# reflow.net
KiCad netlist of a schematic drawn in EAGLE
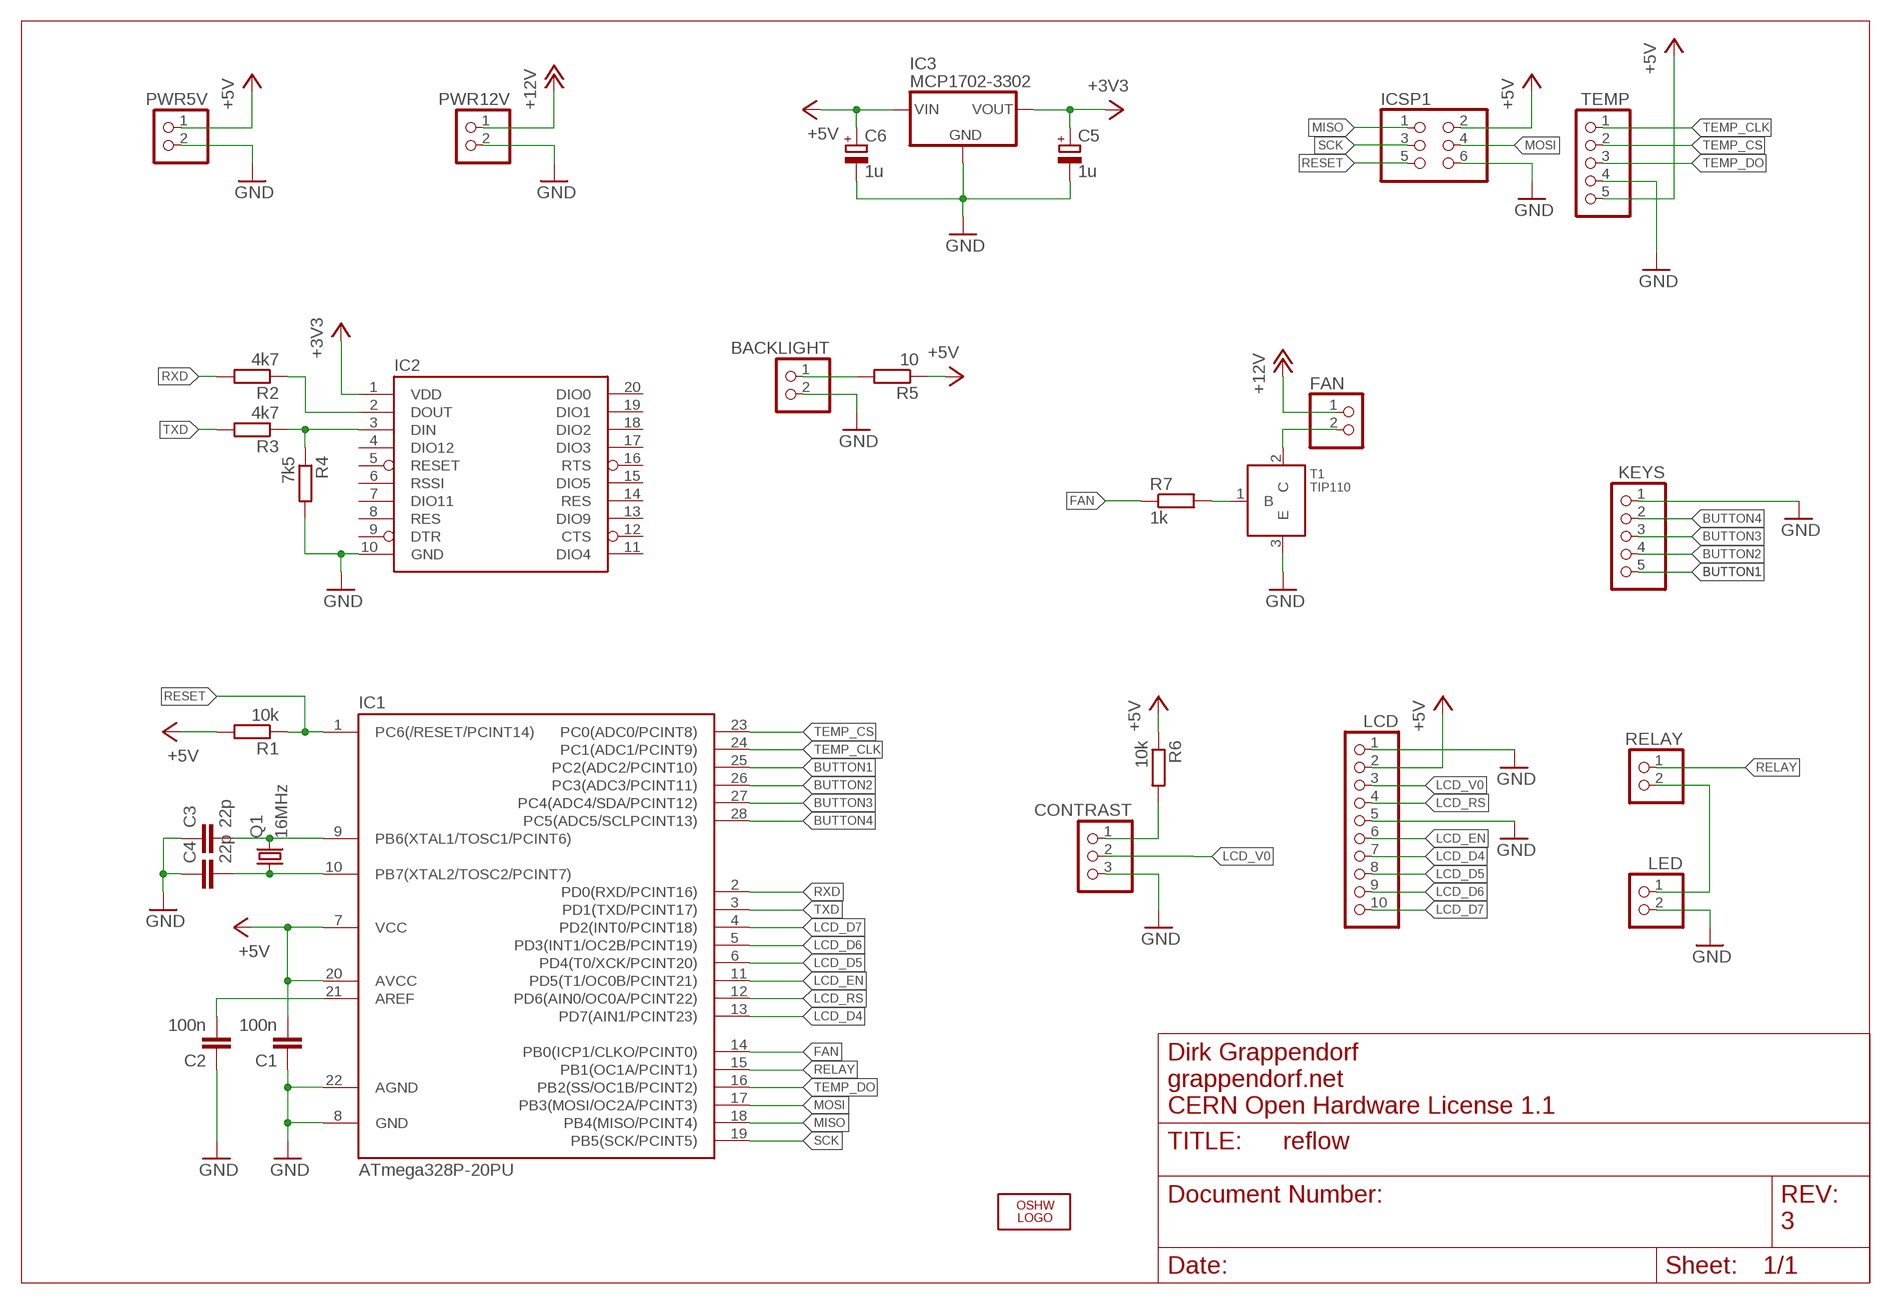
[diagram p0: schematic, sheet 1]

(export (version "E")
  (design (tool "Eeschema 10.0.6"))
  (components
    (comp (ref "BACKLIGHT")
      (value "PINHD-1X2")
      (footprint "eagle-import:1X02")
      (libsource (lib "eagle-import") (part "PINHD-1X2"))
    )
    (comp (ref "C1")
      (value "100n")
      (footprint "eagle-import:C025-024X044")
      (libsource (lib "eagle-import") (part "C-EU025-024X044"))
    )
    (comp (ref "C2")
      (value "100n")
      (footprint "eagle-import:C025-024X044")
      (libsource (lib "eagle-import") (part "C-EU025-024X044"))
    )
    (comp (ref "C3")
      (value "22p")
      (footprint "eagle-import:C025-025X050")
      (libsource (lib "eagle-import") (part "C-EU025-025X050"))
    )
    (comp (ref "C4")
      (value "22p")
      (footprint "eagle-import:C025-025X050")
      (libsource (lib "eagle-import") (part "C-EU025-025X050"))
    )
    (comp (ref "C5")
      (value "1u")
      (footprint "eagle-import:E2,5-5")
      (libsource (lib "eagle-import") (part "CPOL-EUE2.5-5"))
    )
    (comp (ref "C6")
      (value "1u")
      (footprint "eagle-import:E2,5-5")
      (libsource (lib "eagle-import") (part "CPOL-EUE2.5-5"))
    )
    (comp (ref "CONTRAST")
      (value "PINHD-1X3")
      (footprint "eagle-import:1X03")
      (libsource (lib "eagle-import") (part "PINHD-1X3"))
    )
    (comp (ref "FAN")
      (value "PINHD-1X2")
      (footprint "eagle-import:1X02")
      (libsource (lib "eagle-import") (part "PINHD-1X2"))
    )
    (comp (ref "IC1")
      (value "ATmega328P-20PU")
      (footprint "eagle-import:DIL28-3")
      (libsource (lib "eagle-import") (part "ATMEGA48/88/168-PU"))
    )
    (comp (ref "IC2")
      (value "XBEE-1B1")
      (footprint "eagle-import:XBEE-1")
      (libsource (lib "eagle-import") (part "XBEE-1B1"))
    )
    (comp (ref "IC3")
      (value "MCP1702-3302")
      (footprint "eagle-import:MCP1702")
      (libsource (lib "eagle-import") (part "MCP1702"))
    )
    (comp (ref "ICSP1")
      (value "PINHD-2X03_2.54")
      (footprint "eagle-import:2X03")
      (libsource (lib "eagle-import") (part "PINHD-2X03_2.54"))
    )
    (comp (ref "KEYS")
      (value "PINHD-1X5")
      (footprint "eagle-import:1X05")
      (libsource (lib "eagle-import") (part "PINHD-1X5"))
    )
    (comp (ref "LCD")
      (value "PINHD-1X10")
      (footprint "eagle-import:1X10")
      (libsource (lib "eagle-import") (part "PINHD-1X10"))
    )
    (comp (ref "LED")
      (value "PINHD-1X2")
      (footprint "eagle-import:1X02")
      (libsource (lib "eagle-import") (part "PINHD-1X2"))
    )
    (comp (ref "LOGO1")
      (value "OSHW_LOGO_10MILX0350-NT-BOTTOM")
      (footprint "eagle-import:OSHW_10X350_NOTEXT_BOTTOM")
      (libsource (lib "eagle-import") (part "OSHW_LOGO_10MILX0350-NT-BOTTOM"))
    )
    (comp (ref "PWR5V")
      (value "PINHD-1X2")
      (footprint "eagle-import:1X02")
      (libsource (lib "eagle-import") (part "PINHD-1X2"))
    )
    (comp (ref "PWR12V")
      (value "PINHD-1X2")
      (footprint "eagle-import:1X02")
      (libsource (lib "eagle-import") (part "PINHD-1X2"))
    )
    (comp (ref "Q1")
      (value "16MHz")
      (footprint "eagle-import:HC49U-V")
      (libsource (lib "eagle-import") (part "CRYSTALHC49U-V"))
    )
    (comp (ref "R1")
      (value "10k")
      (footprint "eagle-import:0204_7")
      (libsource (lib "eagle-import") (part "R-EU_0204/7"))
    )
    (comp (ref "R2")
      (value "4k7")
      (footprint "eagle-import:0204_7")
      (libsource (lib "eagle-import") (part "R-EU_0204/7"))
    )
    (comp (ref "R3")
      (value "4k7")
      (footprint "eagle-import:0204_7")
      (libsource (lib "eagle-import") (part "R-EU_0204/7"))
    )
    (comp (ref "R4")
      (value "7k5")
      (footprint "eagle-import:0204_7")
      (libsource (lib "eagle-import") (part "R-EU_0204/7"))
    )
    (comp (ref "R5")
      (value "10")
      (footprint "eagle-import:0204_7")
      (libsource (lib "eagle-import") (part "R-EU_0204/7"))
    )
    (comp (ref "R6")
      (value "10k")
      (footprint "eagle-import:0204_7")
      (libsource (lib "eagle-import") (part "R-EU_0204/7"))
    )
    (comp (ref "R7")
      (value "1k")
      (footprint "eagle-import:0204_7")
      (libsource (lib "eagle-import") (part "R-EU_0204/7"))
    )
    (comp (ref "RELAY")
      (value "PINHD-1X2")
      (footprint "eagle-import:1X02")
      (libsource (lib "eagle-import") (part "PINHD-1X2"))
    )
    (comp (ref "T1")
      (value "TIP110")
      (footprint "eagle-import:T0220")
      (libsource (lib "eagle-import") (part "TIP112"))
    )
    (comp (ref "TEMP")
      (value "PINHD-1X5")
      (footprint "eagle-import:1X05")
      (libsource (lib "eagle-import") (part "PINHD-1X5"))
    )
  )
  (nets
    (net (code "1") (name "+3V3") (class "Default")
      (node (ref "C5") (pin "+") (pinfunction "+_+") (pintype "passive"))
      (node (ref "IC2") (pin "1") (pinfunction "VDD_1") (pintype "power_in"))
      (node (ref "IC3") (pin "VOUT") (pinfunction "OUT_VOUT") (pintype "passive"))
    )
    (net (code "2") (name "+5V") (class "Default")
      (node (ref "C1") (pin "2") (pinfunction "2_2") (pintype "passive"))
      (node (ref "C6") (pin "+") (pinfunction "+_+") (pintype "passive"))
      (node (ref "IC1") (pin "20") (pinfunction "AVCC_20") (pintype "passive"))
      (node (ref "IC1") (pin "7") (pinfunction "VCC_7") (pintype "power_in"))
      (node (ref "IC3") (pin "VIN") (pinfunction "IN_VIN") (pintype "input"))
      (node (ref "ICSP1") (pin "2") (pinfunction "2_2") (pintype "passive"))
      (node (ref "LCD") (pin "2") (pinfunction "2_2") (pintype "passive"))
      (node (ref "PWR5V") (pin "1") (pinfunction "1_1") (pintype "passive"))
      (node (ref "R1") (pin "2") (pinfunction "2_2") (pintype "passive"))
      (node (ref "R5") (pin "1") (pinfunction "1_1") (pintype "passive"))
      (node (ref "R6") (pin "1") (pinfunction "1_1") (pintype "passive"))
      (node (ref "TEMP") (pin "5") (pinfunction "5_5") (pintype "passive"))
    )
    (net (code "3") (name "+12V") (class "Default")
      (node (ref "FAN") (pin "1") (pinfunction "1_1") (pintype "passive"))
      (node (ref "PWR12V") (pin "1") (pinfunction "1_1") (pintype "passive"))
    )
    (net (code "4") (name "BUTTON1") (class "Default")
      (node (ref "IC1") (pin "25") (pinfunction "PC2(ADC2/PCINT10)_25") (pintype "bidirectional"))
      (node (ref "KEYS") (pin "5") (pinfunction "5_5") (pintype "passive"))
    )
    (net (code "5") (name "BUTTON2") (class "Default")
      (node (ref "IC1") (pin "26") (pinfunction "PC3(ADC3/PCINT11)_26") (pintype "bidirectional"))
      (node (ref "KEYS") (pin "4") (pinfunction "4_4") (pintype "passive"))
    )
    (net (code "6") (name "BUTTON3") (class "Default")
      (node (ref "IC1") (pin "27") (pinfunction "PC4(ADC4/SDA/PCINT12)_27") (pintype "bidirectional"))
      (node (ref "KEYS") (pin "3") (pinfunction "3_3") (pintype "passive"))
    )
    (net (code "7") (name "BUTTON4") (class "Default")
      (node (ref "IC1") (pin "28") (pinfunction "PC5(ADC5/SCLPCINT13)_28") (pintype "bidirectional"))
      (node (ref "KEYS") (pin "2") (pinfunction "2_2") (pintype "passive"))
    )
    (net (code "8") (name "FAN") (class "Default")
      (node (ref "IC1") (pin "14") (pinfunction "PB0(ICP1/CLKO/PCINT0)_14") (pintype "bidirectional"))
      (node (ref "R7") (pin "1") (pinfunction "1_1") (pintype "passive"))
    )
    (net (code "9") (name "GND") (class "Default")
      (node (ref "BACKLIGHT") (pin "2") (pinfunction "2_2") (pintype "passive"))
      (node (ref "C1") (pin "1") (pinfunction "1_1") (pintype "passive"))
      (node (ref "C2") (pin "1") (pinfunction "1_1") (pintype "passive"))
      (node (ref "C3") (pin "1") (pinfunction "1_1") (pintype "passive"))
      (node (ref "C4") (pin "1") (pinfunction "1_1") (pintype "passive"))
      (node (ref "C5") (pin "-") (pinfunction "-_-") (pintype "passive"))
      (node (ref "C6") (pin "-") (pinfunction "-_-") (pintype "passive"))
      (node (ref "CONTRAST") (pin "3") (pinfunction "3_3") (pintype "passive"))
      (node (ref "IC1") (pin "22") (pinfunction "AGND_22") (pintype "power_in"))
      (node (ref "IC1") (pin "8") (pinfunction "GND_8") (pintype "power_in"))
      (node (ref "IC2") (pin "10") (pinfunction "GND_10") (pintype "power_in"))
      (node (ref "IC3") (pin "GND") (pinfunction "GND_GND") (pintype "input"))
      (node (ref "ICSP1") (pin "6") (pinfunction "6_6") (pintype "passive"))
      (node (ref "KEYS") (pin "1") (pinfunction "1_1") (pintype "passive"))
      (node (ref "LCD") (pin "1") (pinfunction "1_1") (pintype "passive"))
      (node (ref "LCD") (pin "5") (pinfunction "5_5") (pintype "passive"))
      (node (ref "LED") (pin "2") (pinfunction "2_2") (pintype "passive"))
      (node (ref "PWR12V") (pin "2") (pinfunction "2_2") (pintype "passive"))
      (node (ref "PWR5V") (pin "2") (pinfunction "2_2") (pintype "passive"))
      (node (ref "R4") (pin "2") (pinfunction "2_2") (pintype "passive"))
      (node (ref "T1") (pin "3") (pinfunction "E_3") (pintype "bidirectional"))
      (node (ref "TEMP") (pin "4") (pinfunction "4_4") (pintype "passive"))
    )
    (net (code "10") (name "LCD_D4") (class "Default")
      (node (ref "IC1") (pin "13") (pinfunction "PD7(AIN1/PCINT23)_13") (pintype "bidirectional"))
      (node (ref "LCD") (pin "7") (pinfunction "7_7") (pintype "passive"))
    )
    (net (code "11") (name "LCD_D5") (class "Default")
      (node (ref "IC1") (pin "6") (pinfunction "PD4(T0/XCK/PCINT20)_6") (pintype "bidirectional"))
      (node (ref "LCD") (pin "8") (pinfunction "8_8") (pintype "passive"))
    )
    (net (code "12") (name "LCD_D6") (class "Default")
      (node (ref "IC1") (pin "5") (pinfunction "PD3(INT1/OC2B/PCINT19)_5") (pintype "bidirectional"))
      (node (ref "LCD") (pin "9") (pinfunction "9_9") (pintype "passive"))
    )
    (net (code "13") (name "LCD_D7") (class "Default")
      (node (ref "IC1") (pin "4") (pinfunction "PD2(INT0/PCINT18)_4") (pintype "bidirectional"))
      (node (ref "LCD") (pin "10") (pinfunction "10_10") (pintype "passive"))
    )
    (net (code "14") (name "LCD_EN") (class "Default")
      (node (ref "IC1") (pin "11") (pinfunction "PD5(T1/OC0B/PCINT21)_11") (pintype "bidirectional"))
      (node (ref "LCD") (pin "6") (pinfunction "6_6") (pintype "passive"))
    )
    (net (code "15") (name "LCD_RS") (class "Default")
      (node (ref "IC1") (pin "12") (pinfunction "PD6(AIN0/OC0A/PCINT22)_12") (pintype "bidirectional"))
      (node (ref "LCD") (pin "4") (pinfunction "4_4") (pintype "passive"))
    )
    (net (code "16") (name "LCD_V0") (class "Default")
      (node (ref "CONTRAST") (pin "2") (pinfunction "2_2") (pintype "passive"))
      (node (ref "LCD") (pin "3") (pinfunction "3_3") (pintype "passive"))
    )
    (net (code "17") (name "MISO") (class "Default")
      (node (ref "IC1") (pin "18") (pinfunction "PB4(MISO/PCINT4)_18") (pintype "bidirectional"))
      (node (ref "ICSP1") (pin "1") (pinfunction "1_1") (pintype "passive"))
    )
    (net (code "18") (name "MOSI") (class "Default")
      (node (ref "IC1") (pin "17") (pinfunction "PB3(MOSI/OC2A/PCINT3)_17") (pintype "bidirectional"))
      (node (ref "ICSP1") (pin "4") (pinfunction "4_4") (pintype "passive"))
    )
    (net (code "19") (name "Net-(BACKLIGHT-Pad1)") (class "Default")
      (node (ref "BACKLIGHT") (pin "1") (pinfunction "1_1") (pintype "passive"))
      (node (ref "R5") (pin "2") (pinfunction "2_2") (pintype "passive"))
    )
    (net (code "20") (name "Net-(CONTRAST-Pad1)") (class "Default")
      (node (ref "CONTRAST") (pin "1") (pinfunction "1_1") (pintype "passive"))
      (node (ref "R6") (pin "2") (pinfunction "2_2") (pintype "passive"))
    )
    (net (code "21") (name "Net-(IC1-AREF)") (class "Default")
      (node (ref "C2") (pin "2") (pinfunction "2_2") (pintype "passive"))
      (node (ref "IC1") (pin "21") (pinfunction "AREF_21") (pintype "passive"))
    )
    (net (code "22") (name "Net-(IC1-PB6(XTAL1{slash}TOSC1{slash}PCINT6))") (class "Default")
      (node (ref "C3") (pin "2") (pinfunction "2_2") (pintype "passive"))
      (node (ref "IC1") (pin "9") (pinfunction "PB6(XTAL1/TOSC1/PCINT6)_9") (pintype "bidirectional"))
      (node (ref "Q1") (pin "2") (pinfunction "2_2") (pintype "passive"))
    )
    (net (code "23") (name "Net-(IC1-PB7(XTAL2{slash}TOSC2{slash}PCINT7))") (class "Default")
      (node (ref "C4") (pin "2") (pinfunction "2_2") (pintype "passive"))
      (node (ref "IC1") (pin "10") (pinfunction "PB7(XTAL2/TOSC2/PCINT7)_10") (pintype "bidirectional"))
      (node (ref "Q1") (pin "1") (pinfunction "1_1") (pintype "passive"))
    )
    (net (code "24") (name "Net-(IC2-DIN)") (class "Default")
      (node (ref "IC2") (pin "3") (pinfunction "DIN_3") (pintype "input"))
      (node (ref "R3") (pin "1") (pinfunction "1_1") (pintype "passive"))
      (node (ref "R4") (pin "1") (pinfunction "1_1") (pintype "passive"))
    )
    (net (code "25") (name "Net-(IC2-DOUT)") (class "Default")
      (node (ref "IC2") (pin "2") (pinfunction "DOUT_2") (pintype "output"))
      (node (ref "R2") (pin "1") (pinfunction "1_1") (pintype "passive"))
    )
    (net (code "26") (name "Net-(LED-Pad1)") (class "Default")
      (node (ref "LED") (pin "1") (pinfunction "1_1") (pintype "passive"))
      (node (ref "RELAY") (pin "2") (pinfunction "2_2") (pintype "passive"))
    )
    (net (code "27") (name "Net-(T1-B)") (class "Default")
      (node (ref "R7") (pin "2") (pinfunction "2_2") (pintype "passive"))
      (node (ref "T1") (pin "1") (pinfunction "B_1") (pintype "bidirectional"))
    )
    (net (code "28") (name "Net-(T1-C)") (class "Default")
      (node (ref "FAN") (pin "2") (pinfunction "2_2") (pintype "passive"))
      (node (ref "T1") (pin "2") (pinfunction "C_2") (pintype "bidirectional"))
    )
    (net (code "29") (name "RELAY") (class "Default")
      (node (ref "IC1") (pin "15") (pinfunction "PB1(OC1A/PCINT1)_15") (pintype "bidirectional"))
      (node (ref "RELAY") (pin "1") (pinfunction "1_1") (pintype "passive"))
    )
    (net (code "30") (name "RESET") (class "Default")
      (node (ref "IC1") (pin "1") (pinfunction "PC6(/RESET/PCINT14)_1") (pintype "bidirectional"))
      (node (ref "ICSP1") (pin "5") (pinfunction "5_5") (pintype "passive"))
      (node (ref "R1") (pin "1") (pinfunction "1_1") (pintype "passive"))
    )
    (net (code "31") (name "RXD") (class "Default")
      (node (ref "IC1") (pin "2") (pinfunction "PD0(RXD/PCINT16)_2") (pintype "bidirectional"))
      (node (ref "R2") (pin "2") (pinfunction "2_2") (pintype "passive"))
    )
    (net (code "32") (name "SCK") (class "Default")
      (node (ref "IC1") (pin "19") (pinfunction "PB5(SCK/PCINT5)_19") (pintype "bidirectional"))
      (node (ref "ICSP1") (pin "3") (pinfunction "3_3") (pintype "passive"))
    )
    (net (code "33") (name "TEMP_CLK") (class "Default")
      (node (ref "IC1") (pin "24") (pinfunction "PC1(ADC1/PCINT9)_24") (pintype "bidirectional"))
      (node (ref "TEMP") (pin "1") (pinfunction "1_1") (pintype "passive"))
    )
    (net (code "34") (name "TEMP_CS") (class "Default")
      (node (ref "IC1") (pin "23") (pinfunction "PC0(ADC0/PCINT8)_23") (pintype "bidirectional"))
      (node (ref "TEMP") (pin "2") (pinfunction "2_2") (pintype "passive"))
    )
    (net (code "35") (name "TEMP_DO") (class "Default")
      (node (ref "IC1") (pin "16") (pinfunction "PB2(SS/OC1B/PCINT2)_16") (pintype "bidirectional"))
      (node (ref "TEMP") (pin "3") (pinfunction "3_3") (pintype "passive"))
    )
    (net (code "36") (name "TXD") (class "Default")
      (node (ref "IC1") (pin "3") (pinfunction "PD1(TXD/PCINT17)_3") (pintype "bidirectional"))
      (node (ref "R3") (pin "2") (pinfunction "2_2") (pintype "passive"))
    )
    (net (code "37") (name "unconnected-(IC2-CTS-Pad12)") (class "Default")
      (node (ref "IC2") (pin "12") (pinfunction "CTS_12") (pintype "output"))
    )
    (net (code "38") (name "unconnected-(IC2-DIO0-Pad20)") (class "Default")
      (node (ref "IC2") (pin "20") (pinfunction "DIO0_20") (pintype "bidirectional"))
    )
    (net (code "39") (name "unconnected-(IC2-DIO1-Pad19)") (class "Default")
      (node (ref "IC2") (pin "19") (pinfunction "DIO1_19") (pintype "bidirectional"))
    )
    (net (code "40") (name "unconnected-(IC2-DIO2-Pad18)") (class "Default")
      (node (ref "IC2") (pin "18") (pinfunction "DIO2_18") (pintype "bidirectional"))
    )
    (net (code "41") (name "unconnected-(IC2-DIO3-Pad17)") (class "Default")
      (node (ref "IC2") (pin "17") (pinfunction "DIO3_17") (pintype "bidirectional"))
    )
    (net (code "42") (name "unconnected-(IC2-DIO4-Pad11)") (class "Default")
      (node (ref "IC2") (pin "11") (pinfunction "DIO4_11") (pintype "bidirectional"))
    )
    (net (code "43") (name "unconnected-(IC2-DIO5-Pad15)") (class "Default")
      (node (ref "IC2") (pin "15") (pinfunction "DIO5_15") (pintype "bidirectional"))
    )
    (net (code "44") (name "unconnected-(IC2-DIO9-Pad13)") (class "Default")
      (node (ref "IC2") (pin "13") (pinfunction "DIO9_13") (pintype "bidirectional"))
    )
    (net (code "45") (name "unconnected-(IC2-DIO11-Pad7)") (class "Default")
      (node (ref "IC2") (pin "7") (pinfunction "DIO11_7") (pintype "bidirectional"))
    )
    (net (code "46") (name "unconnected-(IC2-DIO12-Pad4)") (class "Default")
      (node (ref "IC2") (pin "4") (pinfunction "DIO12_4") (pintype "bidirectional"))
    )
    (net (code "47") (name "unconnected-(IC2-DTR-Pad9)") (class "Default")
      (node (ref "IC2") (pin "9") (pinfunction "DTR_9") (pintype "bidirectional"))
    )
    (net (code "48") (name "unconnected-(IC2-RES-Pad8)") (class "Default")
      (node (ref "IC2") (pin "8") (pinfunction "RES_8") (pintype "bidirectional"))
    )
    (net (code "49") (name "unconnected-(IC2-RES-Pad14)") (class "Default")
      (node (ref "IC2") (pin "14") (pinfunction "RES_14") (pintype "bidirectional"))
    )
    (net (code "50") (name "unconnected-(IC2-RESET-Pad5)") (class "Default")
      (node (ref "IC2") (pin "5") (pinfunction "RESET_5") (pintype "input"))
    )
    (net (code "51") (name "unconnected-(IC2-RSSI-Pad6)") (class "Default")
      (node (ref "IC2") (pin "6") (pinfunction "RSSI_6") (pintype "bidirectional"))
    )
    (net (code "52") (name "unconnected-(IC2-RTS-Pad16)") (class "Default")
      (node (ref "IC2") (pin "16") (pinfunction "RTS_16") (pintype "input"))
    )
  )
)
